# 2.net
KiCad netlist of a schematic drawn in Altium Designer
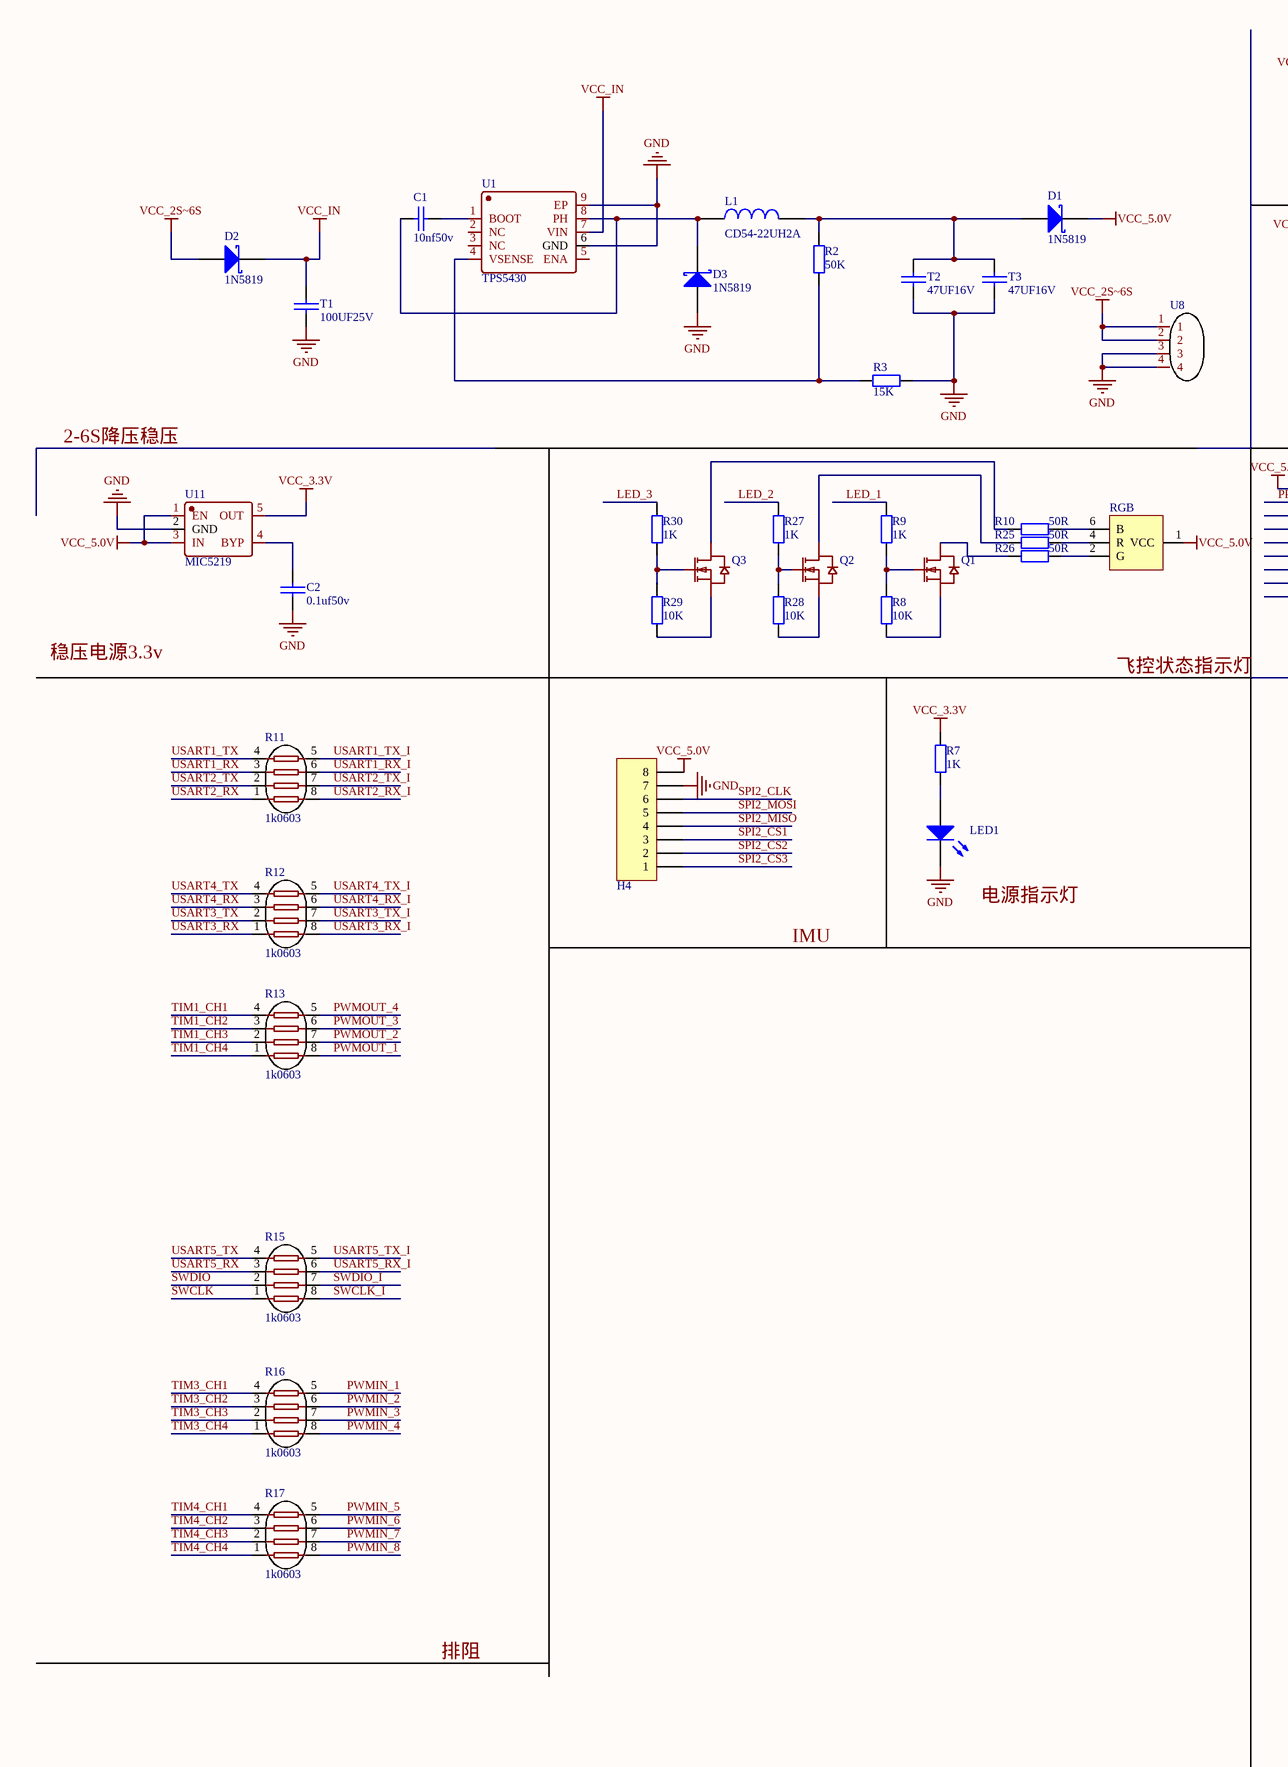
[diagram p0: 飞控板2.SchDoc, left]
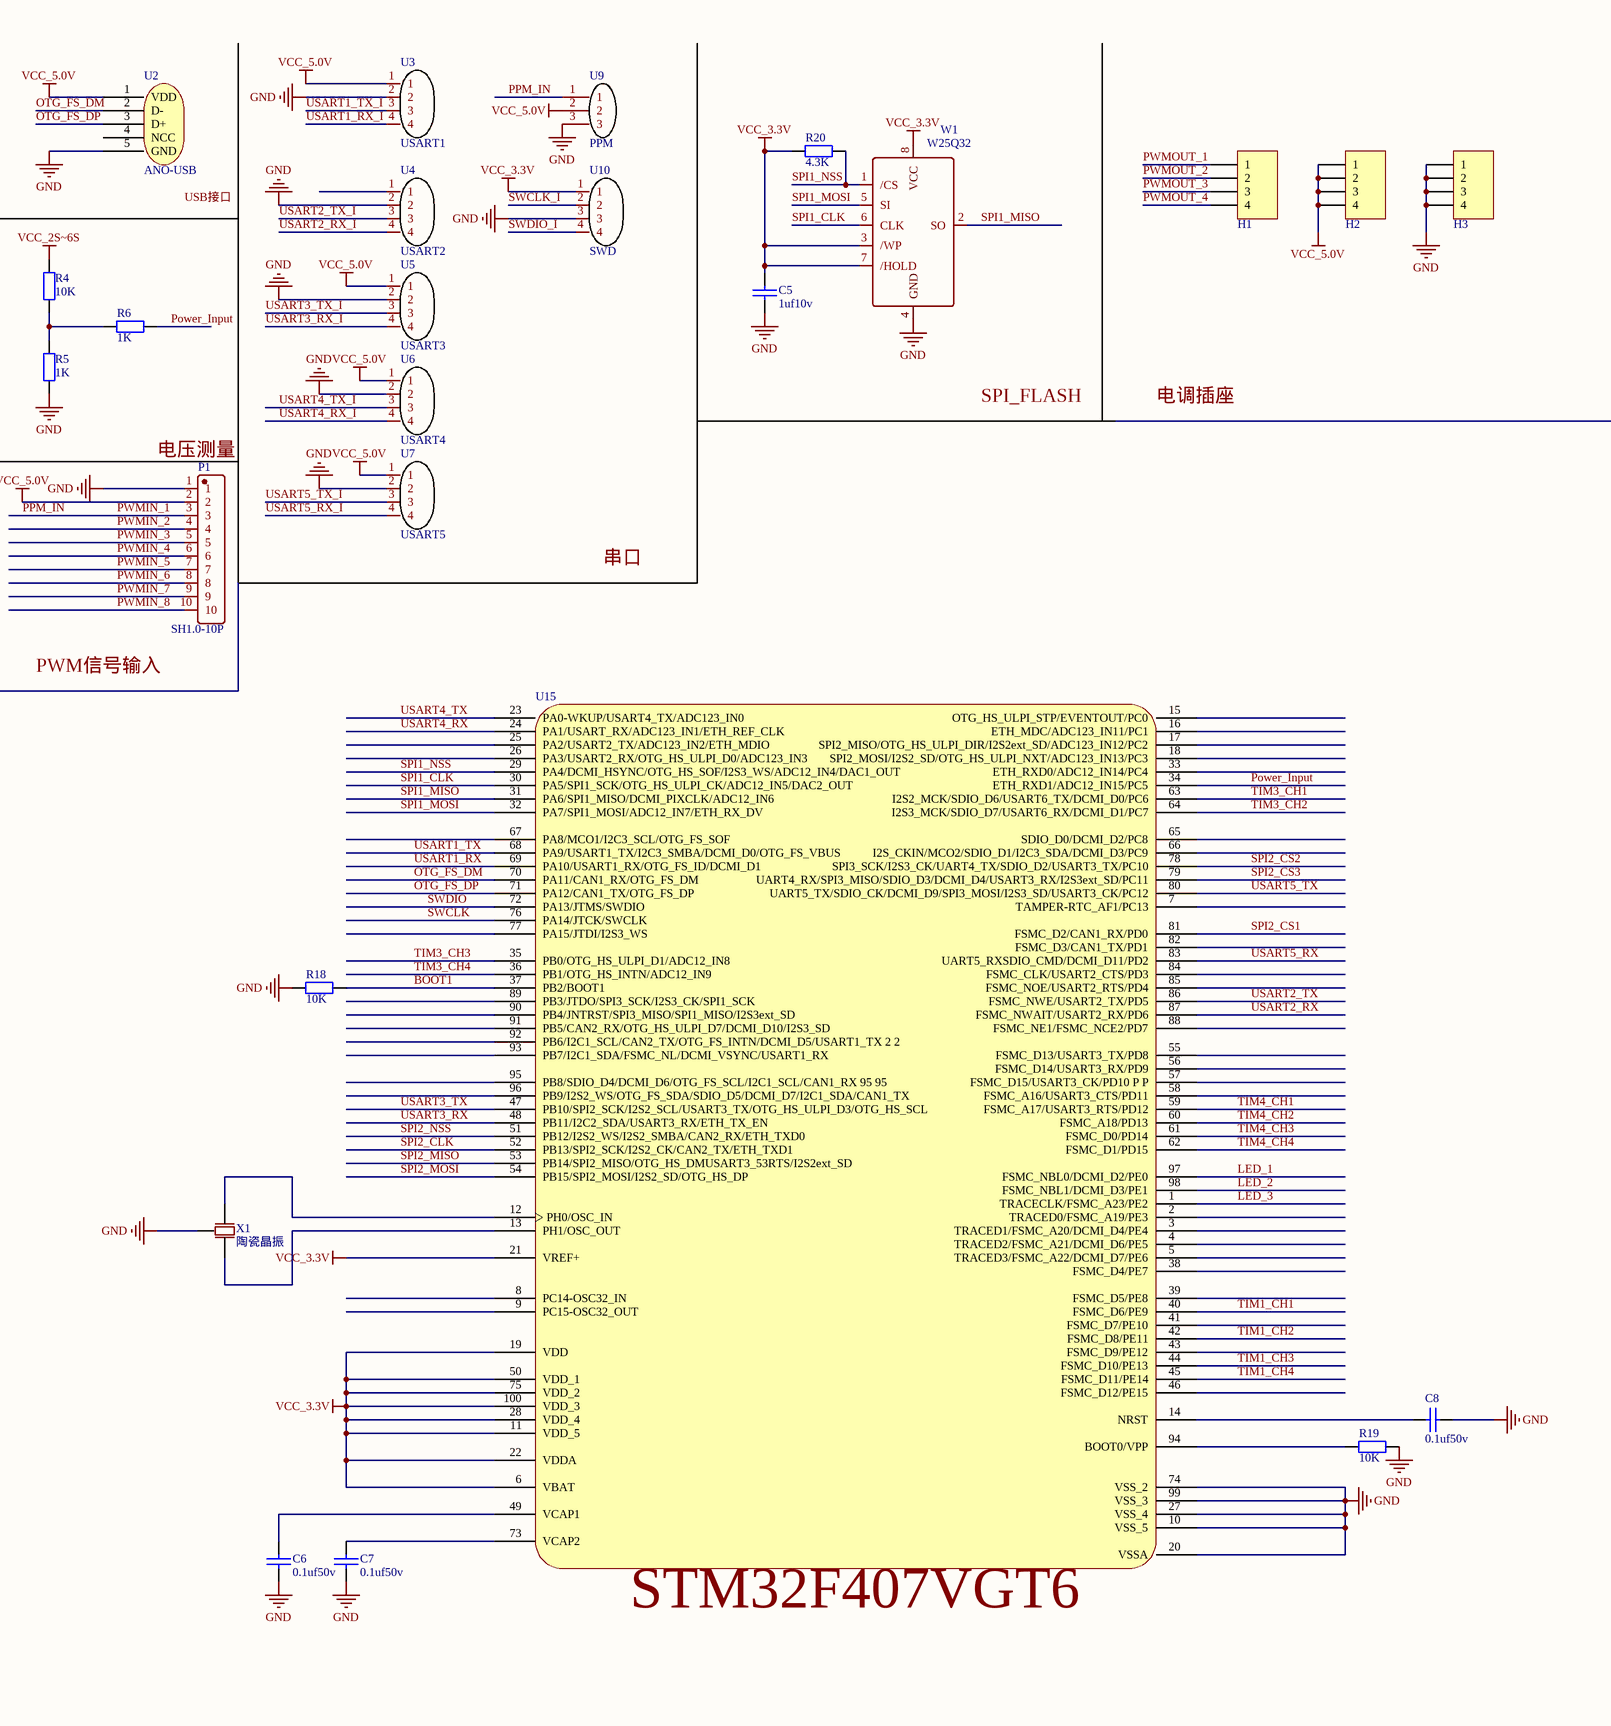
[diagram p1: 飞控板2.SchDoc, right]

(export (version "E")
  (design (tool "Eeschema 10.0.6"))
  (components
    (comp (ref "C1")
      (value "10nf50v")
      (footprint "0805C")
      (description "无极性电容")
      (libsource (lib "电容") (part "CAP"))
    )
    (comp (ref "C2")
      (value "0.1uf50v")
      (footprint "0805C")
      (description "无极性电容")
      (libsource (lib "电容") (part "CAP"))
    )
    (comp (ref "C5")
      (value "1uf10v")
      (footprint "0805C")
      (description "无极性电容")
      (libsource (lib "电容") (part "CAP"))
    )
    (comp (ref "C6")
      (value "0.1uf50v")
      (footprint "0805C")
      (description "无极性电容")
      (libsource (lib "电容") (part "CAP"))
    )
    (comp (ref "C7")
      (value "0.1uf50v")
      (footprint "0805C")
      (description "无极性电容")
      (libsource (lib "电容") (part "CAP"))
    )
    (comp (ref "C8")
      (value "0.1uf50v")
      (footprint "0805C")
      (description "无极性电容")
      (libsource (lib "电容") (part "CAP"))
    )
    (comp (ref "D1")
      (value "1N5819")
      (footprint "DO214AC_SMA")
      (description "贴片肖特基二极管")
      (libsource (lib "1.二极管") (part "1N5817-5819SMD"))
    )
    (comp (ref "D2")
      (value "1N5819")
      (footprint "DO214AC_SMA")
      (description "贴片肖特基二极管")
      (libsource (lib "1.二极管") (part "1N5817-5819SMD"))
    )
    (comp (ref "D3")
      (value "1N5819")
      (footprint "DO214AC_SMA")
      (description "贴片肖特基二极管")
      (libsource (lib "1.二极管") (part "1N5817-5819SMD"))
    )
    (comp (ref "H1")
      (value "Header 4")
      (footprint "HDR1X4")
      (description "Header, 4-Pin")
      (fields (field (name "PUBLISHER") "Altium Limited"))
      (libsource (lib "9.接插件 连接器") (part "Header 4"))
    )
    (comp (ref "H2")
      (value "Header 4")
      (footprint "HDR1X4")
      (description "Header, 4-Pin")
      (fields (field (name "PUBLISHER") "Altium Limited"))
      (libsource (lib "9.接插件 连接器") (part "Header 4"))
    )
    (comp (ref "H3")
      (value "Header 4")
      (footprint "HDR1X4")
      (description "Header, 4-Pin")
      (fields (field (name "PUBLISHER") "Altium Limited"))
      (libsource (lib "9.接插件 连接器") (part "Header 4"))
    )
    (comp (ref "H4")
      (value "Header 8")
      (footprint "HDR1X8")
      (description "Header, 8-Pin")
      (fields (field (name "PUBLISHER") "Altium Limited"))
      (libsource (lib "9.接插件 连接器") (part "Header 8"))
    )
    (comp (ref "L1")
      (value "CD54-22UH2A")
      (footprint "CDRH73")
      (description "INDUCTOR")
      (libsource (lib "电感") (part "INDUCTOR"))
    )
    (comp (ref "LED1") (value "~") (footprint "LED-1206") (libsource (lib "1.二极管") (part "LED1206")))
    (comp (ref "P1")
      (value "SH1.0-10P")
      (footprint "SH1.0-10P")
      (libsource (lib "SH1.0-10P") (part "SH1.0-10P"))
    )
    (comp (ref "Q1") (value "~") (footprint "SI2310") (libsource (lib "SI2310") (part "SI2310")))
    (comp (ref "Q2") (value "~") (footprint "SI2310") (libsource (lib "SI2310") (part "SI2310")))
    (comp (ref "Q3") (value "~") (footprint "SI2310") (libsource (lib "SI2310") (part "SI2310")))
    (comp (ref "R2")
      (value "50K")
      (footprint "0805R")
      (description "0805贴片电阻")
      (libsource (lib "") (part "Res_0805_1"))
    )
    (comp (ref "R3")
      (value "15K")
      (footprint "0805R")
      (description "0805贴片电阻")
      (libsource (lib "0.电阻电容电感") (part "Res_0805"))
    )
    (comp (ref "R4")
      (value "10K")
      (footprint "0805R")
      (description "0805贴片电阻")
      (libsource (lib "") (part "Res_0805_1"))
    )
    (comp (ref "R5")
      (value "1K")
      (footprint "0805R")
      (description "0805贴片电阻")
      (libsource (lib "") (part "Res_0805_1"))
    )
    (comp (ref "R6")
      (value "1K")
      (footprint "0805R")
      (description "0805贴片电阻")
      (libsource (lib "0.电阻电容电感") (part "Res_0805"))
    )
    (comp (ref "R7")
      (value "1K")
      (footprint "0805R")
      (description "0805贴片电阻")
      (libsource (lib "") (part "Res_0805_1"))
    )
    (comp (ref "R8")
      (value "10K")
      (footprint "0805R")
      (description "0805贴片电阻")
      (libsource (lib "") (part "Res_0805_1"))
    )
    (comp (ref "R9")
      (value "1K")
      (footprint "0805R")
      (description "0805贴片电阻")
      (libsource (lib "") (part "Res_0805_1"))
    )
    (comp (ref "R10")
      (value "50R")
      (footprint "0805R")
      (description "0805贴片电阻")
      (libsource (lib "") (part "Res_0805_2"))
    )
    (comp (ref "R11") (value "1k0603") (footprint "1k0603") (libsource (lib "1k0603") (part "1k0603")))
    (comp (ref "R12") (value "1k0603") (footprint "1k0603") (libsource (lib "1k0603") (part "1k0603")))
    (comp (ref "R13") (value "1k0603") (footprint "1k0603") (libsource (lib "1k0603") (part "1k0603")))
    (comp (ref "R15") (value "1k0603") (footprint "1k0603") (libsource (lib "1k0603") (part "1k0603")))
    (comp (ref "R16") (value "1k0603") (footprint "1k0603") (libsource (lib "1k0603") (part "1k0603")))
    (comp (ref "R17") (value "1k0603") (footprint "1k0603") (libsource (lib "1k0603") (part "1k0603")))
    (comp (ref "R18")
      (value "10K")
      (footprint "0805R")
      (description "0805贴片电阻")
      (libsource (lib "") (part "Res_0805_2"))
    )
    (comp (ref "R19")
      (value "10K")
      (footprint "0805R")
      (description "0805贴片电阻")
      (libsource (lib "") (part "Res_0805_2"))
    )
    (comp (ref "R20")
      (value "4.3K")
      (footprint "0805R")
      (description "0805贴片电阻")
      (libsource (lib "") (part "Res_0805_2"))
    )
    (comp (ref "R25")
      (value "50R")
      (footprint "0805R")
      (description "0805贴片电阻")
      (libsource (lib "") (part "Res_0805_2"))
    )
    (comp (ref "R26")
      (value "50R")
      (footprint "0805R")
      (description "0805贴片电阻")
      (libsource (lib "") (part "Res_0805_2"))
    )
    (comp (ref "R27")
      (value "1K")
      (footprint "0805R")
      (description "0805贴片电阻")
      (libsource (lib "") (part "Res_0805_1"))
    )
    (comp (ref "R28")
      (value "10K")
      (footprint "0805R")
      (description "0805贴片电阻")
      (libsource (lib "") (part "Res_0805_1"))
    )
    (comp (ref "R29")
      (value "10K")
      (footprint "0805R")
      (description "0805贴片电阻")
      (libsource (lib "") (part "Res_0805_1"))
    )
    (comp (ref "R30")
      (value "1K")
      (footprint "0805R")
      (description "0805贴片电阻")
      (libsource (lib "") (part "Res_0805_1"))
    )
    (comp (ref "RGB")
      (value "~")
      (footprint "RGB_LED")
      (description "RGB")
      (libsource (lib "RGB灯") (part "RGB"))
    )
    (comp (ref "T1")
      (value "100UF25V")
      (footprint "0805C")
      (description "无极性电容")
      (libsource (lib "电容") (part "CAP"))
    )
    (comp (ref "T2")
      (value "47UF16V")
      (footprint "0805C")
      (description "无极性电容")
      (libsource (lib "电容") (part "CAP"))
    )
    (comp (ref "T3")
      (value "47UF16V")
      (footprint "0805C")
      (description "无极性电容")
      (libsource (lib "电容") (part "CAP"))
    )
    (comp (ref "U1") (value "TPS5430") (footprint "TPS5430") (libsource (lib "TPS5430") (part "TPS5430")))
    (comp (ref "U2") (value "ANO-USB") (footprint "ANO-USB") (libsource (lib "ANO-USB") (part "ANO-USB")))
    (comp (ref "U3") (value "USART1") (footprint "SH1.0-4P") (libsource (lib "SH1.0-4P") (part "SH1.0-4P")))
    (comp (ref "U4") (value "USART2") (footprint "SH1.0-4P") (libsource (lib "SH1.0-4P") (part "SH1.0-4P")))
    (comp (ref "U5") (value "USART3") (footprint "SH1.0-4P") (libsource (lib "SH1.0-4P") (part "SH1.0-4P")))
    (comp (ref "U6") (value "USART4") (footprint "SH1.0-4P") (libsource (lib "SH1.0-4P") (part "SH1.0-4P")))
    (comp (ref "U7") (value "USART5") (footprint "SH1.0-4P") (libsource (lib "SH1.0-4P") (part "SH1.0-4P")))
    (comp (ref "U8") (value "~") (footprint "SH1.0-4P") (libsource (lib "SH1.0-4P") (part "SH1.0-4P")))
    (comp (ref "U9") (value "PPM") (footprint "SH1.0-3P") (libsource (lib "SH1.0-3P") (part "SH1.0-3P")))
    (comp (ref "U10") (value "SWD") (footprint "SH1.0-4P") (libsource (lib "SH1.0-4P") (part "SH1.0-4P")))
    (comp (ref "U11") (value "MIC5219") (footprint "MIC5219") (libsource (lib "MIC5219") (part "MIC5219")))
    (comp (ref "U15")
      (value "~")
      (footprint "STM32F407VGT6=")
      (libsource (lib "STM32F407VGT6=") (part "STM32F407VGT6="))
    )
    (comp (ref "W1") (value "W25Q32") (footprint "W25Q32") (libsource (lib "W25Q32") (part "W25Q32")))
    (comp (ref "X1") (value "陶瓷晶振") (footprint "陶瓷晶振") (libsource (lib "陶瓷晶振") (part "陶瓷晶振")))
  )
  (nets
    (net (code "2") (name "/BOOT1") (class "Default")
      (node (ref "R18") (pin "1") (pinfunction "1_1") (pintype "passive"))
      (node (ref "U15") (pin "37") (pinfunction "PB2/BOOT1_37") (pintype "passive"))
    )
    (net (code "4") (name "/LED_1") (class "Default")
      (node (ref "R9") (pin "1") (pinfunction "1_1") (pintype "passive"))
      (node (ref "U15") (pin "97") (pinfunction "FSMC_NBL0/DCMI_D2/PE0_97") (pintype "passive"))
    )
    (net (code "5") (name "/LED_2") (class "Default")
      (node (ref "R27") (pin "1") (pinfunction "1_1") (pintype "passive"))
      (node (ref "U15") (pin "98") (pinfunction "FSMC_NBL1/DCMI_D3/PE1_98") (pintype "passive"))
    )
    (net (code "6") (name "/LED_3") (class "Default")
      (node (ref "R30") (pin "1") (pinfunction "1_1") (pintype "passive"))
      (node (ref "U15") (pin "1") (pinfunction "TRACECLK/FSMC_A23/PE2_1") (pintype "passive"))
    )
    (net (code "7") (name "/OTG_FS_DM") (class "Default")
      (node (ref "U15") (pin "70") (pinfunction "PA11/CAN1_RX/OTG_FS_DM_70") (pintype "passive"))
      (node (ref "U2") (pin "2") (pinfunction "D-_2") (pintype "passive"))
    )
    (net (code "8") (name "/OTG_FS_DP") (class "Default")
      (node (ref "U15") (pin "71") (pinfunction "PA12/CAN1_TX/OTG_FS_DP_71") (pintype "passive"))
      (node (ref "U2") (pin "3") (pinfunction "D+_3") (pintype "passive"))
    )
    (net (code "9") (name "/PPM_IN") (class "Default")
      (node (ref "P1") (pin "3") (pinfunction "3_3") (pintype "passive"))
      (node (ref "R16") (pin "5") (pinfunction "5_5") (pintype "passive"))
      (node (ref "U9") (pin "1") (pinfunction "1_1") (pintype "passive"))
    )
    (net (code "10") (name "/PWMIN_2") (class "Default")
      (node (ref "P1") (pin "4") (pinfunction "4_4") (pintype "passive"))
      (node (ref "R16") (pin "6") (pinfunction "6_6") (pintype "passive"))
    )
    (net (code "11") (name "/PWMIN_3") (class "Default")
      (node (ref "P1") (pin "5") (pinfunction "5_5") (pintype "passive"))
      (node (ref "R16") (pin "7") (pinfunction "7_7") (pintype "passive"))
    )
    (net (code "12") (name "/PWMIN_4") (class "Default")
      (node (ref "P1") (pin "6") (pinfunction "6_6") (pintype "passive"))
      (node (ref "R16") (pin "8") (pinfunction "8_8") (pintype "passive"))
    )
    (net (code "13") (name "/PWMIN_5") (class "Default")
      (node (ref "P1") (pin "7") (pinfunction "7_7") (pintype "passive"))
      (node (ref "R17") (pin "5") (pinfunction "5_5") (pintype "passive"))
    )
    (net (code "14") (name "/PWMIN_6") (class "Default")
      (node (ref "P1") (pin "8") (pinfunction "8_8") (pintype "passive"))
      (node (ref "R17") (pin "6") (pinfunction "6_6") (pintype "passive"))
    )
    (net (code "15") (name "/PWMIN_7") (class "Default")
      (node (ref "P1") (pin "9") (pinfunction "9_9") (pintype "passive"))
      (node (ref "R17") (pin "7") (pinfunction "7_7") (pintype "passive"))
    )
    (net (code "16") (name "/PWMIN_8") (class "Default")
      (node (ref "P1") (pin "10") (pinfunction "10_10") (pintype "passive"))
      (node (ref "R17") (pin "8") (pinfunction "8_8") (pintype "passive"))
    )
    (net (code "17") (name "/PWMOUT_1") (class "Default")
      (node (ref "H1") (pin "1") (pinfunction "1_1") (pintype "passive"))
      (node (ref "R13") (pin "8") (pinfunction "8_8") (pintype "passive"))
    )
    (net (code "18") (name "/PWMOUT_2") (class "Default")
      (node (ref "H1") (pin "2") (pinfunction "2_2") (pintype "passive"))
      (node (ref "R13") (pin "7") (pinfunction "7_7") (pintype "passive"))
    )
    (net (code "19") (name "/PWMOUT_3") (class "Default")
      (node (ref "H1") (pin "3") (pinfunction "3_3") (pintype "passive"))
      (node (ref "R13") (pin "6") (pinfunction "6_6") (pintype "passive"))
    )
    (net (code "20") (name "/PWMOUT_4") (class "Default")
      (node (ref "H1") (pin "4") (pinfunction "4_4") (pintype "passive"))
      (node (ref "R13") (pin "5") (pinfunction "5_5") (pintype "passive"))
    )
    (net (code "22") (name "/Power_Input") (class "Default")
      (node (ref "R6") (pin "2") (pinfunction "2_2") (pintype "passive"))
      (node (ref "U15") (pin "34") (pinfunction "ETH_RXD1/ADC12_IN15/PC5_34") (pintype "passive"))
    )
    (net (code "23") (name "/SPI1_CLK") (class "Default")
      (node (ref "U15") (pin "30") (pinfunction "PA5/SPI1_SCK/OTG_HS_ULPI_CK/ADC12_IN5/DAC2_OUT_30") (pintype "passive"))
      (node (ref "W1") (pin "6") (pinfunction "CLK_6") (pintype "passive"))
    )
    (net (code "24") (name "/SPI1_MISO") (class "Default")
      (node (ref "U15") (pin "31") (pinfunction "PA6/SPI1_MISO/DCMI_PIXCLK/ADC12_IN6_31") (pintype "passive"))
      (node (ref "W1") (pin "2") (pinfunction "SO_2") (pintype "passive"))
    )
    (net (code "25") (name "/SPI1_MOSI") (class "Default")
      (node (ref "U15") (pin "32") (pinfunction "PA7/SPI1_MOSI/ADC12_IN7/ETH_RX_DV_32") (pintype "passive"))
      (node (ref "W1") (pin "5") (pinfunction "SI_5") (pintype "passive"))
    )
    (net (code "26") (name "/SPI1_NSS") (class "Default")
      (node (ref "R20") (pin "1") (pinfunction "1_1") (pintype "passive"))
      (node (ref "U15") (pin "29") (pinfunction "PA4/DCMI_HSYNC/OTG_HS_SOF/I2S3_WS/ADC12_IN4/DAC1_OUT_29") (pintype "passive"))
      (node (ref "W1") (pin "1") (pinfunction "/CS_1") (pintype "passive"))
    )
    (net (code "27") (name "/SPI2_CLK") (class "Default")
      (node (ref "H4") (pin "6") (pinfunction "6_6") (pintype "passive"))
      (node (ref "U15") (pin "52") (pinfunction "PB13/SPI2_SCK/I2S2_CK/CAN2_TX/ETH_TXD1_52") (pintype "passive"))
    )
    (net (code "28") (name "/SPI2_CS1") (class "Default")
      (node (ref "H4") (pin "3") (pinfunction "3_3") (pintype "passive"))
      (node (ref "U15") (pin "81") (pinfunction "FSMC_D2/CAN1_RX/PD0_81") (pintype "passive"))
    )
    (net (code "29") (name "/SPI2_CS2") (class "Default")
      (node (ref "H4") (pin "2") (pinfunction "2_2") (pintype "passive"))
      (node (ref "U15") (pin "78") (pinfunction "SPI3_SCK/I2S3_CK/UART4_TX/SDIO_D2/USART3_TX/PC10_78") (pintype "passive"))
    )
    (net (code "30") (name "/SPI2_CS3") (class "Default")
      (node (ref "H4") (pin "1") (pinfunction "1_1") (pintype "passive"))
      (node (ref "U15") (pin "79") (pinfunction "UART4_RX/SPI3_MISO/SDIO_D3/DCMI_D4/USART3_RX/I2S3ext_SD/PC11_79") (pintype "passive"))
    )
    (net (code "31") (name "/SPI2_MISO") (class "Default")
      (node (ref "H4") (pin "4") (pinfunction "4_4") (pintype "passive"))
      (node (ref "U15") (pin "53") (pinfunction "PB14/SPI2_MISO/OTG_HS_DMUSART3_53RTS/I2S2ext_SD_53") (pintype "passive"))
    )
    (net (code "32") (name "/SPI2_MOSI") (class "Default")
      (node (ref "H4") (pin "5") (pinfunction "5_5") (pintype "passive"))
      (node (ref "U15") (pin "54") (pinfunction "PB15/SPI2_MOSI/I2S2_SD/OTG_HS_DP_54") (pintype "passive"))
    )
    (net (code "33") (name "/SPI2_NSS") (class "Default")
      (node (ref "U15") (pin "51") (pinfunction "PB12/I2S2_WS/I2S2_SMBA/CAN2_RX/ETH_TXD0_51") (pintype "passive"))
    )
    (net (code "36") (name "/SWCLK") (class "Default")
      (node (ref "R15") (pin "1") (pinfunction "1_1") (pintype "passive"))
      (node (ref "U15") (pin "76") (pinfunction "PA14/JTCK/SWCLK_76") (pintype "passive"))
    )
    (net (code "37") (name "/SWCLK_I") (class "Default")
      (node (ref "R15") (pin "8") (pinfunction "8_8") (pintype "passive"))
      (node (ref "U10") (pin "2") (pinfunction "2_2") (pintype "passive"))
    )
    (net (code "38") (name "/SWDIO") (class "Default")
      (node (ref "R15") (pin "2") (pinfunction "2_2") (pintype "passive"))
      (node (ref "U15") (pin "72") (pinfunction "PA13/JTMS/SWDIO_72") (pintype "passive"))
    )
    (net (code "39") (name "/SWDIO_I") (class "Default")
      (node (ref "R15") (pin "7") (pinfunction "7_7") (pintype "passive"))
      (node (ref "U10") (pin "4") (pinfunction "4_4") (pintype "passive"))
    )
    (net (code "40") (name "/TIM1_CH1") (class "Default")
      (node (ref "R13") (pin "4") (pinfunction "4_4") (pintype "passive"))
      (node (ref "U15") (pin "40") (pinfunction "FSMC_D6/PE9_40") (pintype "passive"))
    )
    (net (code "41") (name "/TIM1_CH2") (class "Default")
      (node (ref "R13") (pin "3") (pinfunction "3_3") (pintype "passive"))
      (node (ref "U15") (pin "42") (pinfunction "FSMC_D8/PE11_42") (pintype "passive"))
    )
    (net (code "42") (name "/TIM1_CH3") (class "Default")
      (node (ref "R13") (pin "2") (pinfunction "2_2") (pintype "passive"))
      (node (ref "U15") (pin "44") (pinfunction "FSMC_D10/PE13_44") (pintype "passive"))
    )
    (net (code "43") (name "/TIM1_CH4") (class "Default")
      (node (ref "R13") (pin "1") (pinfunction "1_1") (pintype "passive"))
      (node (ref "U15") (pin "45") (pinfunction "FSMC_D11/PE14_45") (pintype "passive"))
    )
    (net (code "44") (name "/TIM3_CH1") (class "Default")
      (node (ref "R16") (pin "4") (pinfunction "4_4") (pintype "passive"))
      (node (ref "U15") (pin "63") (pinfunction "I2S2_MCK/SDIO_D6/USART6_TX/DCMI_D0/PC6_63") (pintype "passive"))
    )
    (net (code "45") (name "/TIM3_CH2") (class "Default")
      (node (ref "R16") (pin "3") (pinfunction "3_3") (pintype "passive"))
      (node (ref "U15") (pin "64") (pinfunction "I2S3_MCK/SDIO_D7/USART6_RX/DCMI_D1/PC7_64") (pintype "passive"))
    )
    (net (code "46") (name "/TIM3_CH3") (class "Default")
      (node (ref "R16") (pin "2") (pinfunction "2_2") (pintype "passive"))
      (node (ref "U15") (pin "35") (pinfunction "PB0/OTG_HS_ULPI_D1/ADC12_IN8_35") (pintype "passive"))
    )
    (net (code "47") (name "/TIM3_CH4") (class "Default")
      (node (ref "R16") (pin "1") (pinfunction "1_1") (pintype "passive"))
      (node (ref "U15") (pin "36") (pinfunction "PB1/OTG_HS_INTN/ADC12_IN9_36") (pintype "passive"))
    )
    (net (code "48") (name "/TIM4_CH1") (class "Default")
      (node (ref "R17") (pin "4") (pinfunction "4_4") (pintype "passive"))
      (node (ref "U15") (pin "59") (pinfunction "FSMC_A17/USART3_RTS/PD12_59") (pintype "passive"))
    )
    (net (code "49") (name "/TIM4_CH2") (class "Default")
      (node (ref "R17") (pin "3") (pinfunction "3_3") (pintype "passive"))
      (node (ref "U15") (pin "60") (pinfunction "FSMC_A18/PD13_60") (pintype "passive"))
    )
    (net (code "50") (name "/TIM4_CH3") (class "Default")
      (node (ref "R17") (pin "2") (pinfunction "2_2") (pintype "passive"))
      (node (ref "U15") (pin "61") (pinfunction "FSMC_D0/PD14_61") (pintype "passive"))
    )
    (net (code "51") (name "/TIM4_CH4") (class "Default")
      (node (ref "R17") (pin "1") (pinfunction "1_1") (pintype "passive"))
      (node (ref "U15") (pin "62") (pinfunction "FSMC_D1/PD15_62") (pintype "passive"))
    )
    (net (code "52") (name "/USART1_RX") (class "Default")
      (node (ref "R11") (pin "3") (pinfunction "3_3") (pintype "passive"))
      (node (ref "U15") (pin "69") (pinfunction "PA10/USART1_RX/OTG_FS_ID/DCMI_D1_69") (pintype "passive"))
    )
    (net (code "53") (name "/USART1_RX_I") (class "Default")
      (node (ref "R11") (pin "6") (pinfunction "6_6") (pintype "passive"))
      (node (ref "U3") (pin "4") (pinfunction "4_4") (pintype "passive"))
    )
    (net (code "54") (name "/USART1_TX") (class "Default")
      (node (ref "R11") (pin "4") (pinfunction "4_4") (pintype "passive"))
      (node (ref "U15") (pin "68") (pinfunction "PA9/USART1_TX/I2C3_SMBA/DCMI_D0/OTG_FS_VBUS_68") (pintype "passive"))
    )
    (net (code "55") (name "/USART1_TX_I") (class "Default")
      (node (ref "R11") (pin "5") (pinfunction "5_5") (pintype "passive"))
      (node (ref "U3") (pin "3") (pinfunction "3_3") (pintype "passive"))
    )
    (net (code "56") (name "/USART2_RX") (class "Default")
      (node (ref "R11") (pin "1") (pinfunction "1_1") (pintype "passive"))
      (node (ref "U15") (pin "87") (pinfunction "FSMC_NWAIT/USART2_RX/PD6_87") (pintype "passive"))
    )
    (net (code "57") (name "/USART2_RX_I") (class "Default")
      (node (ref "R11") (pin "8") (pinfunction "8_8") (pintype "passive"))
      (node (ref "U4") (pin "4") (pinfunction "4_4") (pintype "passive"))
    )
    (net (code "58") (name "/USART2_TX") (class "Default")
      (node (ref "R11") (pin "2") (pinfunction "2_2") (pintype "passive"))
      (node (ref "U15") (pin "86") (pinfunction "FSMC_NWE/USART2_TX/PD5_86") (pintype "passive"))
    )
    (net (code "59") (name "/USART2_TX_I") (class "Default")
      (node (ref "R11") (pin "7") (pinfunction "7_7") (pintype "passive"))
      (node (ref "U4") (pin "3") (pinfunction "3_3") (pintype "passive"))
    )
    (net (code "60") (name "/USART3_RX") (class "Default")
      (node (ref "R12") (pin "1") (pinfunction "1_1") (pintype "passive"))
      (node (ref "U15") (pin "48") (pinfunction "PB11/I2C2_SDA/USART3_RX/ETH_TX_EN_48") (pintype "passive"))
    )
    (net (code "61") (name "/USART3_RX_I") (class "Default")
      (node (ref "R12") (pin "8") (pinfunction "8_8") (pintype "passive"))
      (node (ref "U5") (pin "4") (pinfunction "4_4") (pintype "passive"))
    )
    (net (code "62") (name "/USART3_TX") (class "Default")
      (node (ref "R12") (pin "2") (pinfunction "2_2") (pintype "passive"))
      (node (ref "U15") (pin "47") (pinfunction "PB10/SPI2_SCK/I2S2_SCL/USART3_TX/OTG_HS_ULPI_D3/OTG_HS_SCL_47") (pintype "passive"))
    )
    (net (code "63") (name "/USART3_TX_I") (class "Default")
      (node (ref "R12") (pin "7") (pinfunction "7_7") (pintype "passive"))
      (node (ref "U5") (pin "3") (pinfunction "3_3") (pintype "passive"))
    )
    (net (code "64") (name "/USART4_RX") (class "Default")
      (node (ref "R12") (pin "3") (pinfunction "3_3") (pintype "passive"))
      (node (ref "U15") (pin "24") (pinfunction "PA1/USART_RX/ADC123_IN1/ETH_REF_CLK_24") (pintype "passive"))
    )
    (net (code "65") (name "/USART4_RX_I") (class "Default")
      (node (ref "R12") (pin "6") (pinfunction "6_6") (pintype "passive"))
      (node (ref "U6") (pin "4") (pinfunction "4_4") (pintype "passive"))
    )
    (net (code "66") (name "/USART4_TX") (class "Default")
      (node (ref "R12") (pin "4") (pinfunction "4_4") (pintype "passive"))
      (node (ref "U15") (pin "23") (pinfunction "PA0-WKUP/USART4_TX/ADC123_IN0_23") (pintype "passive"))
    )
    (net (code "67") (name "/USART4_TX_I") (class "Default")
      (node (ref "R12") (pin "5") (pinfunction "5_5") (pintype "passive"))
      (node (ref "U6") (pin "3") (pinfunction "3_3") (pintype "passive"))
    )
    (net (code "68") (name "/USART5_RX") (class "Default")
      (node (ref "R15") (pin "3") (pinfunction "3_3") (pintype "passive"))
      (node (ref "U15") (pin "83") (pinfunction "UART5_RXSDIO_CMD/DCMI_D11/PD2_83") (pintype "passive"))
    )
    (net (code "69") (name "/USART5_RX_I") (class "Default")
      (node (ref "R15") (pin "6") (pinfunction "6_6") (pintype "passive"))
      (node (ref "U7") (pin "4") (pinfunction "4_4") (pintype "passive"))
    )
    (net (code "70") (name "/USART5_TX") (class "Default")
      (node (ref "R15") (pin "4") (pinfunction "4_4") (pintype "passive"))
      (node (ref "U15") (pin "80") (pinfunction "UART5_TX/SDIO_CK/DCMI_D9/SPI3_MOSI/I2S3_SD/USART3_CK/PC12_80") (pintype "passive"))
    )
    (net (code "71") (name "/USART5_TX_I") (class "Default")
      (node (ref "R15") (pin "5") (pinfunction "5_5") (pintype "passive"))
      (node (ref "U7") (pin "3") (pinfunction "3_3") (pintype "passive"))
    )
    (net (code "80") (name "GND") (class "Default")
      (node (ref "C2") (pin "1") (pinfunction "1_1") (pintype "passive"))
      (node (ref "C5") (pin "1") (pinfunction "1_1") (pintype "passive"))
      (node (ref "C6") (pin "1") (pinfunction "1_1") (pintype "passive"))
      (node (ref "C7") (pin "1") (pinfunction "1_1") (pintype "passive"))
      (node (ref "C8") (pin "2") (pinfunction "2_2") (pintype "passive"))
      (node (ref "D3") (pin "1") (pinfunction "A_1") (pintype "passive"))
      (node (ref "H3") (pin "1") (pinfunction "1_1") (pintype "passive"))
      (node (ref "H3") (pin "2") (pinfunction "2_2") (pintype "passive"))
      (node (ref "H3") (pin "3") (pinfunction "3_3") (pintype "passive"))
      (node (ref "H3") (pin "4") (pinfunction "4_4") (pintype "passive"))
      (node (ref "H4") (pin "7") (pinfunction "7_7") (pintype "passive"))
      (node (ref "LED1") (pin "2") (pinfunction "K_2") (pintype "passive"))
      (node (ref "P1") (pin "1") (pinfunction "1_1") (pintype "passive"))
      (node (ref "R18") (pin "2") (pinfunction "2_2") (pintype "passive"))
      (node (ref "R19") (pin "1") (pinfunction "1_1") (pintype "passive"))
      (node (ref "R3") (pin "2") (pinfunction "2_2") (pintype "passive"))
      (node (ref "R5") (pin "2") (pinfunction "2_2") (pintype "passive"))
      (node (ref "T1") (pin "2") (pinfunction "2_2") (pintype "passive"))
      (node (ref "T2") (pin "2") (pinfunction "2_2") (pintype "passive"))
      (node (ref "T3") (pin "2") (pinfunction "2_2") (pintype "passive"))
      (node (ref "U1") (pin "6") (pinfunction "GND_6") (pintype "passive"))
      (node (ref "U1") (pin "9") (pinfunction "EP_9") (pintype "passive"))
      (node (ref "U10") (pin "3") (pinfunction "3_3") (pintype "passive"))
      (node (ref "U11") (pin "2") (pinfunction "GND_2") (pintype "passive"))
      (node (ref "U15") (pin "10") (pinfunction "VSS_5_10") (pintype "passive"))
      (node (ref "U15") (pin "20") (pinfunction "VSSA_20") (pintype "passive"))
      (node (ref "U15") (pin "27") (pinfunction "VSS_4_27") (pintype "passive"))
      (node (ref "U15") (pin "74") (pinfunction "VSS_2_74") (pintype "passive"))
      (node (ref "U15") (pin "99") (pinfunction "VSS_3_99") (pintype "passive"))
      (node (ref "U2") (pin "5") (pinfunction "GND_5") (pintype "passive"))
      (node (ref "U3") (pin "2") (pinfunction "2_2") (pintype "passive"))
      (node (ref "U4") (pin "2") (pinfunction "2_2") (pintype "passive"))
      (node (ref "U5") (pin "2") (pinfunction "2_2") (pintype "passive"))
      (node (ref "U6") (pin "2") (pinfunction "2_2") (pintype "passive"))
      (node (ref "U7") (pin "2") (pinfunction "2_2") (pintype "passive"))
      (node (ref "U8") (pin "3") (pinfunction "3_3") (pintype "passive"))
      (node (ref "U8") (pin "4") (pinfunction "4_4") (pintype "passive"))
      (node (ref "U9") (pin "3") (pinfunction "3_3") (pintype "passive"))
      (node (ref "W1") (pin "4") (pinfunction "GND_4") (pintype "passive"))
      (node (ref "X1") (pin "2") (pinfunction "GND_2") (pintype "passive"))
    )
    (net (code "81") (name "Net-(D1-A)") (class "Default")
      (node (ref "D1") (pin "1") (pinfunction "A_1") (pintype "passive"))
      (node (ref "L1") (pin "2") (pinfunction "2_2") (pintype "passive"))
      (node (ref "R2") (pin "1") (pinfunction "1_1") (pintype "passive"))
      (node (ref "T2") (pin "1") (pinfunction "1_1") (pintype "passive"))
      (node (ref "T3") (pin "1") (pinfunction "1_1") (pintype "passive"))
    )
    (net (code "82") (name "Net-(D3-K)") (class "Default")
      (node (ref "C1") (pin "1") (pinfunction "1_1") (pintype "passive"))
      (node (ref "D3") (pin "2") (pinfunction "K_2") (pintype "passive"))
      (node (ref "L1") (pin "1") (pinfunction "1_1") (pintype "passive"))
      (node (ref "U1") (pin "8") (pinfunction "PH_8") (pintype "passive"))
    )
    (net (code "83") (name "Net-(LED1-A)") (class "Default")
      (node (ref "LED1") (pin "1") (pinfunction "A_1") (pintype "passive"))
      (node (ref "R7") (pin "2") (pinfunction "2_2") (pintype "passive"))
    )
    (net (code "84") (name "Net-(Q1-D)") (class "Default")
      (node (ref "Q1") (pin "3") (pinfunction "D_3") (pintype "passive"))
      (node (ref "R26") (pin "2") (pinfunction "2_2") (pintype "passive"))
    )
    (net (code "85") (name "Net-(Q1-G)") (class "Default")
      (node (ref "Q1") (pin "1") (pinfunction "G_1") (pintype "passive"))
      (node (ref "R8") (pin "1") (pinfunction "1_1") (pintype "passive"))
      (node (ref "R9") (pin "2") (pinfunction "2_2") (pintype "passive"))
    )
    (net (code "86") (name "Net-(Q1-S)") (class "Default")
      (node (ref "Q1") (pin "2") (pinfunction "S_2") (pintype "passive"))
      (node (ref "R8") (pin "2") (pinfunction "2_2") (pintype "passive"))
    )
    (net (code "87") (name "Net-(Q2-D)") (class "Default")
      (node (ref "Q2") (pin "3") (pinfunction "D_3") (pintype "passive"))
      (node (ref "R25") (pin "2") (pinfunction "2_2") (pintype "passive"))
    )
    (net (code "88") (name "Net-(Q2-G)") (class "Default")
      (node (ref "Q2") (pin "1") (pinfunction "G_1") (pintype "passive"))
      (node (ref "R27") (pin "2") (pinfunction "2_2") (pintype "passive"))
      (node (ref "R28") (pin "1") (pinfunction "1_1") (pintype "passive"))
    )
    (net (code "89") (name "Net-(Q2-S)") (class "Default")
      (node (ref "Q2") (pin "2") (pinfunction "S_2") (pintype "passive"))
      (node (ref "R28") (pin "2") (pinfunction "2_2") (pintype "passive"))
    )
    (net (code "90") (name "Net-(Q3-D)") (class "Default")
      (node (ref "Q3") (pin "3") (pinfunction "D_3") (pintype "passive"))
      (node (ref "R10") (pin "2") (pinfunction "2_2") (pintype "passive"))
    )
    (net (code "91") (name "Net-(Q3-G)") (class "Default")
      (node (ref "Q3") (pin "1") (pinfunction "G_1") (pintype "passive"))
      (node (ref "R29") (pin "1") (pinfunction "1_1") (pintype "passive"))
      (node (ref "R30") (pin "2") (pinfunction "2_2") (pintype "passive"))
    )
    (net (code "92") (name "Net-(Q3-S)") (class "Default")
      (node (ref "Q3") (pin "2") (pinfunction "S_2") (pintype "passive"))
      (node (ref "R29") (pin "2") (pinfunction "2_2") (pintype "passive"))
    )
    (net (code "93") (name "Net-(R4-Pad2)") (class "Default")
      (node (ref "R4") (pin "2") (pinfunction "2_2") (pintype "passive"))
      (node (ref "R5") (pin "1") (pinfunction "1_1") (pintype "passive"))
      (node (ref "R6") (pin "1") (pinfunction "1_1") (pintype "passive"))
    )
    (net (code "94") (name "Net-(RGB-B)") (class "Default")
      (node (ref "R10") (pin "1") (pinfunction "1_1") (pintype "passive"))
      (node (ref "RGB") (pin "6") (pinfunction "B_6") (pintype "passive"))
    )
    (net (code "95") (name "Net-(RGB-G)") (class "Default")
      (node (ref "R26") (pin "1") (pinfunction "1_1") (pintype "passive"))
      (node (ref "RGB") (pin "2") (pinfunction "G_2") (pintype "passive"))
    )
    (net (code "96") (name "Net-(RGB-R)") (class "Default")
      (node (ref "R25") (pin "1") (pinfunction "1_1") (pintype "passive"))
      (node (ref "RGB") (pin "4") (pinfunction "R_4") (pintype "passive"))
    )
    (net (code "97") (name "Net-(U1-BOOT)") (class "Default")
      (node (ref "C1") (pin "2") (pinfunction "2_2") (pintype "passive"))
      (node (ref "U1") (pin "1") (pinfunction "BOOT_1") (pintype "passive"))
    )
    (net (code "98") (name "Net-(U1-VSENSE)") (class "Default")
      (node (ref "R2") (pin "2") (pinfunction "2_2") (pintype "passive"))
      (node (ref "R3") (pin "1") (pinfunction "1_1") (pintype "passive"))
      (node (ref "U1") (pin "4") (pinfunction "VSENSE_4") (pintype "passive"))
    )
    (net (code "99") (name "Net-(U11-BYP)") (class "Default")
      (node (ref "C2") (pin "2") (pinfunction "2_2") (pintype "passive"))
      (node (ref "U11") (pin "4") (pinfunction "BYP_4") (pintype "passive"))
    )
    (net (code "100") (name "Net-(U15-BOOT0{slash}VPP)") (class "Default")
      (node (ref "R19") (pin "2") (pinfunction "2_2") (pintype "passive"))
      (node (ref "U15") (pin "94") (pinfunction "BOOT0/VPP_94") (pintype "passive"))
    )
    (net (code "101") (name "Net-(U15-NRST)") (class "Default")
      (node (ref "C8") (pin "1") (pinfunction "1_1") (pintype "passive"))
      (node (ref "U15") (pin "14") (pinfunction "NRST_14") (pintype "passive"))
    )
    (net (code "102") (name "Net-(U15-PH0{slash}OSC_IN)") (class "Default")
      (node (ref "U15") (pin "12") (pinfunction "PH0/OSC_IN_12") (pintype "passive"))
      (node (ref "X1") (pin "3") (pinfunction "OSC2_3") (pintype "passive"))
    )
    (net (code "103") (name "Net-(U15-PH1{slash}OSC_OUT)") (class "Default")
      (node (ref "U15") (pin "13") (pinfunction "PH1/OSC_OUT_13") (pintype "passive"))
      (node (ref "X1") (pin "1") (pinfunction "OSC1_1") (pintype "passive"))
    )
    (net (code "104") (name "Net-(U15-VCAP1)") (class "Default")
      (node (ref "C6") (pin "2") (pinfunction "2_2") (pintype "passive"))
      (node (ref "U15") (pin "49") (pinfunction "VCAP1_49") (pintype "passive"))
    )
    (net (code "105") (name "Net-(U15-VCAP2)") (class "Default")
      (node (ref "C7") (pin "2") (pinfunction "2_2") (pintype "passive"))
      (node (ref "U15") (pin "73") (pinfunction "VCAP2_73") (pintype "passive"))
    )
    (net (code "106") (name "VCC_2S~6S") (class "Default")
      (node (ref "D2") (pin "1") (pinfunction "A_1") (pintype "passive"))
      (node (ref "R4") (pin "1") (pinfunction "1_1") (pintype "passive"))
      (node (ref "U8") (pin "1") (pinfunction "1_1") (pintype "passive"))
      (node (ref "U8") (pin "2") (pinfunction "2_2") (pintype "passive"))
    )
    (net (code "107") (name "VCC_3.3V") (class "Default")
      (node (ref "C5") (pin "2") (pinfunction "2_2") (pintype "passive"))
      (node (ref "R20") (pin "2") (pinfunction "2_2") (pintype "passive"))
      (node (ref "R7") (pin "1") (pinfunction "1_1") (pintype "passive"))
      (node (ref "U10") (pin "1") (pinfunction "1_1") (pintype "passive"))
      (node (ref "U11") (pin "5") (pinfunction "OUT_5") (pintype "passive"))
      (node (ref "U15") (pin "100") (pinfunction "VDD_3_100") (pintype "passive"))
      (node (ref "U15") (pin "11") (pinfunction "VDD_5_11") (pintype "passive"))
      (node (ref "U15") (pin "19") (pinfunction "VDD_19") (pintype "passive"))
      (node (ref "U15") (pin "21") (pinfunction "VREF+_21") (pintype "passive"))
      (node (ref "U15") (pin "22") (pinfunction "VDDA_22") (pintype "passive"))
      (node (ref "U15") (pin "28") (pinfunction "VDD_4_28") (pintype "passive"))
      (node (ref "U15") (pin "50") (pinfunction "VDD_1_50") (pintype "passive"))
      (node (ref "U15") (pin "6") (pinfunction "VBAT_6") (pintype "passive"))
      (node (ref "U15") (pin "75") (pinfunction "VDD_2_75") (pintype "passive"))
      (node (ref "W1") (pin "3") (pinfunction "/WP_3") (pintype "passive"))
      (node (ref "W1") (pin "7") (pinfunction "/HOLD_7") (pintype "passive"))
      (node (ref "W1") (pin "8") (pinfunction "VCC_8") (pintype "passive"))
    )
    (net (code "108") (name "VCC_5.0V") (class "Default")
      (node (ref "D1") (pin "2") (pinfunction "K_2") (pintype "passive"))
      (node (ref "H2") (pin "1") (pinfunction "1_1") (pintype "passive"))
      (node (ref "H2") (pin "2") (pinfunction "2_2") (pintype "passive"))
      (node (ref "H2") (pin "3") (pinfunction "3_3") (pintype "passive"))
      (node (ref "H2") (pin "4") (pinfunction "4_4") (pintype "passive"))
      (node (ref "H4") (pin "8") (pinfunction "8_8") (pintype "passive"))
      (node (ref "P1") (pin "2") (pinfunction "2_2") (pintype "passive"))
      (node (ref "RGB") (pin "1") (pinfunction "VCC_1") (pintype "passive"))
      (node (ref "U11") (pin "1") (pinfunction "EN_1") (pintype "passive"))
      (node (ref "U11") (pin "3") (pinfunction "IN_3") (pintype "passive"))
      (node (ref "U2") (pin "1") (pinfunction "VDD_1") (pintype "passive"))
      (node (ref "U3") (pin "1") (pinfunction "1_1") (pintype "passive"))
      (node (ref "U5") (pin "1") (pinfunction "1_1") (pintype "passive"))
      (node (ref "U6") (pin "1") (pinfunction "1_1") (pintype "passive"))
      (node (ref "U7") (pin "1") (pinfunction "1_1") (pintype "passive"))
      (node (ref "U9") (pin "2") (pinfunction "2_2") (pintype "passive"))
    )
    (net (code "109") (name "VCC_IN") (class "Default")
      (node (ref "D2") (pin "2") (pinfunction "K_2") (pintype "passive"))
      (node (ref "T1") (pin "1") (pinfunction "1_1") (pintype "passive"))
      (node (ref "U1") (pin "7") (pinfunction "VIN_7") (pintype "passive"))
    )
    (net (code "110") (name "unconnected-(U1-ENA-Pad5)") (class "Default")
      (node (ref "U1") (pin "5") (pinfunction "ENA_5") (pintype "passive"))
    )
    (net (code "111") (name "unconnected-(U1-NC-Pad2)") (class "Default")
      (node (ref "U1") (pin "2") (pinfunction "NC_2") (pintype "passive"))
    )
    (net (code "112") (name "unconnected-(U1-NC-Pad3)") (class "Default")
      (node (ref "U1") (pin "3") (pinfunction "NC_3") (pintype "passive"))
    )
    (net (code "113") (name "unconnected-(U2-NCC-Pad4)") (class "Default")
      (node (ref "U2") (pin "4") (pinfunction "NCC_4") (pintype "passive"))
    )
    (net (code "114") (name "unconnected-(U4-Pad1)") (class "Default")
      (node (ref "U4") (pin "1") (pinfunction "1_1") (pintype "passive"))
    )
    (net (code "115") (name "unconnected-(U15-ETH_MDC{slash}ADC123_IN11{slash}PC1-Pad16)") (class "Default")
      (node (ref "U15") (pin "16") (pinfunction "ETH_MDC/ADC123_IN11/PC1_16") (pintype "passive"))
    )
    (net (code "116") (name "unconnected-(U15-ETH_RXD0{slash}ADC12_IN14{slash}PC4-Pad33)") (class "Default")
      (node (ref "U15") (pin "33") (pinfunction "ETH_RXD0/ADC12_IN14/PC4_33") (pintype "passive"))
    )
    (net (code "117") (name "unconnected-(U15-FSMC_A16{slash}USART3_CTS{slash}PD11-Pad58)") (class "Default")
      (node (ref "U15") (pin "58") (pinfunction "FSMC_A16/USART3_CTS/PD11_58") (pintype "passive"))
    )
    (net (code "118") (name "unconnected-(U15-FSMC_CLK{slash}USART2_CTS{slash}PD3-Pad84)") (class "Default")
      (node (ref "U15") (pin "84") (pinfunction "FSMC_CLK/USART2_CTS/PD3_84") (pintype "passive"))
    )
    (net (code "119") (name "unconnected-(U15-FSMC_D3{slash}CAN1_TX{slash}PD1-Pad82)") (class "Default")
      (node (ref "U15") (pin "82") (pinfunction "FSMC_D3/CAN1_TX/PD1_82") (pintype "passive"))
    )
    (net (code "120") (name "unconnected-(U15-FSMC_D4{slash}PE7-Pad38)") (class "Default")
      (node (ref "U15") (pin "38") (pinfunction "FSMC_D4/PE7_38") (pintype "passive"))
    )
    (net (code "121") (name "unconnected-(U15-FSMC_D5{slash}PE8-Pad39)") (class "Default")
      (node (ref "U15") (pin "39") (pinfunction "FSMC_D5/PE8_39") (pintype "passive"))
    )
    (net (code "122") (name "unconnected-(U15-FSMC_D7{slash}PE10-Pad41)") (class "Default")
      (node (ref "U15") (pin "41") (pinfunction "FSMC_D7/PE10_41") (pintype "passive"))
    )
    (net (code "123") (name "unconnected-(U15-FSMC_D9{slash}PE12-Pad43)") (class "Default")
      (node (ref "U15") (pin "43") (pinfunction "FSMC_D9/PE12_43") (pintype "passive"))
    )
    (net (code "124") (name "unconnected-(U15-FSMC_D12{slash}PE15-Pad46)") (class "Default")
      (node (ref "U15") (pin "46") (pinfunction "FSMC_D12/PE15_46") (pintype "passive"))
    )
    (net (code "125") (name "unconnected-(U15-FSMC_D13{slash}USART3_TX{slash}PD8-Pad55)") (class "Default")
      (node (ref "U15") (pin "55") (pinfunction "FSMC_D13/USART3_TX/PD8_55") (pintype "passive"))
    )
    (net (code "126") (name "unconnected-(U15-FSMC_D14{slash}USART3_RX{slash}PD9-Pad56)") (class "Default")
      (node (ref "U15") (pin "56") (pinfunction "FSMC_D14/USART3_RX/PD9_56") (pintype "passive"))
    )
    (net (code "127") (name "unconnected-(U15-FSMC_D15{slash}USART3_CK{slash}PD10_P_P-Pad57)") (class "Default")
      (node (ref "U15") (pin "57") (pinfunction "FSMC_D15/USART3_CK/PD10_P_P_57") (pintype "passive"))
    )
    (net (code "128") (name "unconnected-(U15-FSMC_NE1{slash}FSMC_NCE2{slash}PD7-Pad88)") (class "Default")
      (node (ref "U15") (pin "88") (pinfunction "FSMC_NE1/FSMC_NCE2/PD7_88") (pintype "passive"))
    )
    (net (code "129") (name "unconnected-(U15-FSMC_NOE{slash}USART2_RTS{slash}PD4-Pad85)") (class "Default")
      (node (ref "U15") (pin "85") (pinfunction "FSMC_NOE/USART2_RTS/PD4_85") (pintype "passive"))
    )
    (net (code "130") (name "unconnected-(U15-I2S_CKIN{slash}MCO2{slash}SDIO_D1{slash}I2C3_SDA{slash}DCMI_D3{slash}PC9-Pad66)") (class "Default")
      (node (ref "U15") (pin "66") (pinfunction "I2S_CKIN/MCO2/SDIO_D1/I2C3_SDA/DCMI_D3/PC9_66") (pintype "passive"))
    )
    (net (code "131") (name "unconnected-(U15-OTG_HS_ULPI_STP{slash}EVENTOUT{slash}PC0-Pad15)") (class "Default")
      (node (ref "U15") (pin "15") (pinfunction "OTG_HS_ULPI_STP/EVENTOUT/PC0_15") (pintype "passive"))
    )
    (net (code "132") (name "unconnected-(U15-PA2{slash}USART2_TX{slash}ADC123_IN2{slash}ETH_MDIO-Pad25)") (class "Default")
      (node (ref "U15") (pin "25") (pinfunction "PA2/USART2_TX/ADC123_IN2/ETH_MDIO_25") (pintype "passive"))
    )
    (net (code "133") (name "unconnected-(U15-PA3{slash}USART2_RX{slash}OTG_HS_ULPI_D0{slash}ADC123_IN3-Pad26)") (class "Default")
      (node (ref "U15") (pin "26") (pinfunction "PA3/USART2_RX/OTG_HS_ULPI_D0/ADC123_IN3_26") (pintype "passive"))
    )
    (net (code "134") (name "unconnected-(U15-PA8{slash}MCO1{slash}I2C3_SCL{slash}OTG_FS_SOF-Pad67)") (class "Default")
      (node (ref "U15") (pin "67") (pinfunction "PA8/MCO1/I2C3_SCL/OTG_FS_SOF_67") (pintype "passive"))
    )
    (net (code "135") (name "unconnected-(U15-PA15{slash}JTDI{slash}I2S3_WS-Pad77)") (class "Default")
      (node (ref "U15") (pin "77") (pinfunction "PA15/JTDI/I2S3_WS_77") (pintype "passive"))
    )
    (net (code "136") (name "unconnected-(U15-PB3{slash}JTDO{slash}SPI3_SCK{slash}I2S3_CK{slash}SPI1_SCK-Pad89)") (class "Default")
      (node (ref "U15") (pin "89") (pinfunction "PB3/JTDO/SPI3_SCK/I2S3_CK/SPI1_SCK_89") (pintype "passive"))
    )
    (net (code "137") (name "unconnected-(U15-PB4{slash}JNTRST{slash}SPI3_MISO{slash}SPI1_MISO{slash}I2S3ext_SD-Pad90)") (class "Default")
      (node (ref "U15") (pin "90") (pinfunction "PB4/JNTRST/SPI3_MISO/SPI1_MISO/I2S3ext_SD_90") (pintype "passive"))
    )
    (net (code "138") (name "unconnected-(U15-PB5{slash}CAN2_RX{slash}OTG_HS_ULPI_D7{slash}DCMI_D10{slash}I2S3_SD-Pad91)") (class "Default")
      (node (ref "U15") (pin "91") (pinfunction "PB5/CAN2_RX/OTG_HS_ULPI_D7/DCMI_D10/I2S3_SD_91") (pintype "passive"))
    )
    (net (code "139") (name "unconnected-(U15-PB6{slash}I2C1_SCL{slash}CAN2_TX{slash}OTG_FS_INTN{slash}DCMI_D5{slash}USART1_TX_2_2-Pad92)") (class "Default")
      (node (ref "U15") (pin "92") (pinfunction "PB6/I2C1_SCL/CAN2_TX/OTG_FS_INTN/DCMI_D5/USART1_TX_2_2_92") (pintype "passive"))
    )
    (net (code "140") (name "unconnected-(U15-PB7{slash}I2C1_SDA{slash}FSMC_NL{slash}DCMI_VSYNC{slash}USART1_RX-Pad93)") (class "Default")
      (node (ref "U15") (pin "93") (pinfunction "PB7/I2C1_SDA/FSMC_NL/DCMI_VSYNC/USART1_RX_93") (pintype "passive"))
    )
    (net (code "141") (name "unconnected-(U15-PB8{slash}SDIO_D4{slash}DCMI_D6{slash}OTG_FS_SCL{slash}I2C1_SCL{slash}CAN1_RX_95_95-Pad95)") (class "Default")
      (node (ref "U15") (pin "95") (pinfunction "PB8/SDIO_D4/DCMI_D6/OTG_FS_SCL/I2C1_SCL/CAN1_RX_95_95_95") (pintype "passive"))
    )
    (net (code "142") (name "unconnected-(U15-PB9{slash}I2S2_WS{slash}OTG_FS_SDA{slash}SDIO_D5{slash}DCMI_D7{slash}I2C1_SDA{slash}CAN1_TX-Pad96)") (class "Default")
      (node (ref "U15") (pin "96") (pinfunction "PB9/I2S2_WS/OTG_FS_SDA/SDIO_D5/DCMI_D7/I2C1_SDA/CAN1_TX_96") (pintype "passive"))
    )
    (net (code "143") (name "unconnected-(U15-PC14-OSC32_IN-Pad8)") (class "Default")
      (node (ref "U15") (pin "8") (pinfunction "PC14-OSC32_IN_8") (pintype "passive"))
    )
    (net (code "144") (name "unconnected-(U15-PC15-OSC32_OUT-Pad9)") (class "Default")
      (node (ref "U15") (pin "9") (pinfunction "PC15-OSC32_OUT_9") (pintype "passive"))
    )
    (net (code "145") (name "unconnected-(U15-SDIO_D0{slash}DCMI_D2{slash}PC8-Pad65)") (class "Default")
      (node (ref "U15") (pin "65") (pinfunction "SDIO_D0/DCMI_D2/PC8_65") (pintype "passive"))
    )
    (net (code "146") (name "unconnected-(U15-SPI2_MISO{slash}OTG_HS_ULPI_DIR{slash}I2S2ext_SD{slash}ADC123_IN12{slash}PC2-Pad17)") (class "Default")
      (node (ref "U15") (pin "17") (pinfunction "SPI2_MISO/OTG_HS_ULPI_DIR/I2S2ext_SD/ADC123_IN12/PC2_17") (pintype "passive"))
    )
    (net (code "147") (name "unconnected-(U15-SPI2_MOSI{slash}I2S2_SD{slash}OTG_HS_ULPI_NXT{slash}ADC123_IN13{slash}PC3-Pad18)") (class "Default")
      (node (ref "U15") (pin "18") (pinfunction "SPI2_MOSI/I2S2_SD/OTG_HS_ULPI_NXT/ADC123_IN13/PC3_18") (pintype "passive"))
    )
    (net (code "148") (name "unconnected-(U15-TAMPER-RTC_AF1{slash}PC13-Pad7)") (class "Default")
      (node (ref "U15") (pin "7") (pinfunction "TAMPER-RTC_AF1/PC13_7") (pintype "passive"))
    )
    (net (code "149") (name "unconnected-(U15-TRACED0{slash}FSMC_A19{slash}PE3-Pad2)") (class "Default")
      (node (ref "U15") (pin "2") (pinfunction "TRACED0/FSMC_A19/PE3_2") (pintype "passive"))
    )
    (net (code "150") (name "unconnected-(U15-TRACED1{slash}FSMC_A20{slash}DCMI_D4{slash}PE4-Pad3)") (class "Default")
      (node (ref "U15") (pin "3") (pinfunction "TRACED1/FSMC_A20/DCMI_D4/PE4_3") (pintype "passive"))
    )
    (net (code "151") (name "unconnected-(U15-TRACED2{slash}FSMC_A21{slash}DCMI_D6{slash}PE5-Pad4)") (class "Default")
      (node (ref "U15") (pin "4") (pinfunction "TRACED2/FSMC_A21/DCMI_D6/PE5_4") (pintype "passive"))
    )
    (net (code "152") (name "unconnected-(U15-TRACED3{slash}FSMC_A22{slash}DCMI_D7{slash}PE6-Pad5)") (class "Default")
      (node (ref "U15") (pin "5") (pinfunction "TRACED3/FSMC_A22/DCMI_D7/PE6_5") (pintype "passive"))
    )
  )
)
